# ICSL_PS_PCC_ATDE.net
KiCad netlist of a schematic drawn in Altium Designer
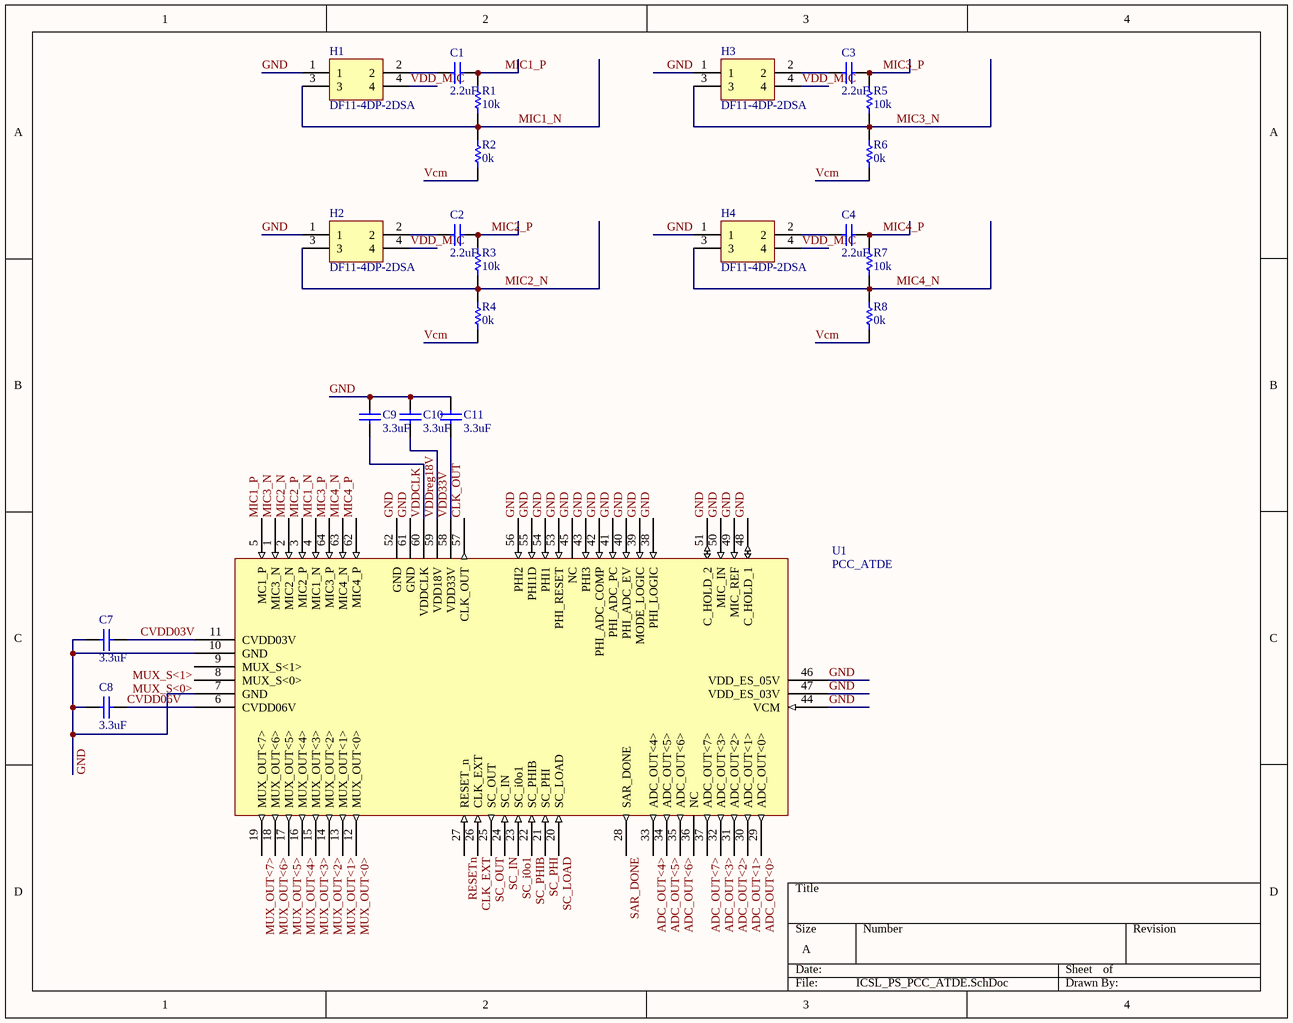
[diagram p0: ICSL_PS_PCC_ATDE.SchDoc]

(export (version "E")
  (design (tool "Eeschema 10.0.6"))
  (components
    (comp (ref "C1")
      (value "2.2uF")
      (footprint "CAPC1608X90X35NL15T15")
      (description "Multilayer Ceramic Capacitors MLCC - SMD/SMT 0603 10uF 4VOLTS X5R 10%")
      (fields (field (name "MANUFACTURER PART NUMBER") "06034D106KAT2A") (field (name "TOLERANCE") "10 %"))
      (libsource (lib "CommunityVault") (part "CMP-4105021-1"))
    )
    (comp (ref "C2")
      (value "2.2uF")
      (footprint "CAPC1608X90X35NL15T15")
      (description "Multilayer Ceramic Capacitors MLCC - SMD/SMT 0603 10uF 4VOLTS X5R 10%")
      (fields (field (name "MANUFACTURER PART NUMBER") "06034D106KAT2A") (field (name "TOLERANCE") "10 %"))
      (libsource (lib "CommunityVault") (part "CMP-4105021-1"))
    )
    (comp (ref "C3")
      (value "2.2uF")
      (footprint "CAPC1608X90X35NL15T15")
      (description "Multilayer Ceramic Capacitors MLCC - SMD/SMT 0603 10uF 4VOLTS X5R 10%")
      (fields (field (name "MANUFACTURER PART NUMBER") "06034D106KAT2A") (field (name "TOLERANCE") "10 %"))
      (libsource (lib "CommunityVault") (part "CMP-4105021-1"))
    )
    (comp (ref "C4")
      (value "2.2uF")
      (footprint "CAPC1608X90X35NL15T15")
      (description "Multilayer Ceramic Capacitors MLCC - SMD/SMT 0603 10uF 4VOLTS X5R 10%")
      (fields (field (name "MANUFACTURER PART NUMBER") "06034D106KAT2A") (field (name "TOLERANCE") "10 %"))
      (libsource (lib "CommunityVault") (part "CMP-4105021-1"))
    )
    (comp (ref "C7")
      (value "3.3uF")
      (footprint "CAPC1608X90X35NL15T15")
      (description "Multilayer Ceramic Capacitors MLCC - SMD/SMT 0603 10uF 4VOLTS X5R 10%")
      (fields (field (name "MANUFACTURER PART NUMBER") "06034D106KAT2A") (field (name "TOLERANCE") "10 %"))
      (libsource (lib "CommunityVault") (part "CMP-4105021-1"))
    )
    (comp (ref "C8")
      (value "3.3uF")
      (footprint "CAPC1608X90X35NL15T15")
      (description "Multilayer Ceramic Capacitors MLCC - SMD/SMT 0603 10uF 4VOLTS X5R 10%")
      (fields (field (name "MANUFACTURER PART NUMBER") "06034D106KAT2A") (field (name "TOLERANCE") "10 %"))
      (libsource (lib "CommunityVault") (part "CMP-4105021-1"))
    )
    (comp (ref "C9")
      (value "3.3uF")
      (footprint "CAPC1608X90X35NL15T15")
      (description "Multilayer Ceramic Capacitors MLCC - SMD/SMT 0603 10uF 4VOLTS X5R 10%")
      (fields (field (name "MANUFACTURER PART NUMBER") "06034D106KAT2A") (field (name "TOLERANCE") "10 %"))
      (libsource (lib "CommunityVault") (part "CMP-4105021-1"))
    )
    (comp (ref "C10")
      (value "3.3uF")
      (footprint "CAPC1608X90X35NL15T15")
      (description "Multilayer Ceramic Capacitors MLCC - SMD/SMT 0603 10uF 4VOLTS X5R 10%")
      (fields (field (name "MANUFACTURER PART NUMBER") "06034D106KAT2A") (field (name "TOLERANCE") "10 %"))
      (libsource (lib "CommunityVault") (part "CMP-4105021-1"))
    )
    (comp (ref "C11")
      (value "3.3uF")
      (footprint "CAPC1608X90X35NL15T15")
      (description "Multilayer Ceramic Capacitors MLCC - SMD/SMT 0603 10uF 4VOLTS X5R 10%")
      (fields (field (name "MANUFACTURER PART NUMBER") "06034D106KAT2A") (field (name "TOLERANCE") "10 %"))
      (libsource (lib "CommunityVault") (part "CMP-4105021-1"))
    )
    (comp (ref "H1")
      (value "DF11-4DP-2DSA")
      (footprint "PCB-xg1cw1zwm1fua28k7qwq-1")
      (description "4 Position 2mm Pitch Dual Row (2x2) Straight Through Hole Pin Header")
      (libsource (lib "Octopart library") (part "SYM-6dfba4f2b6fab23c-1"))
    )
    (comp (ref "H2")
      (value "DF11-4DP-2DSA")
      (footprint "PCB-xg1cw1zwm1fua28k7qwq-1")
      (description "4 Position 2mm Pitch Dual Row (2x2) Straight Through Hole Pin Header")
      (libsource (lib "Octopart library") (part "SYM-6dfba4f2b6fab23c-1"))
    )
    (comp (ref "H3")
      (value "DF11-4DP-2DSA")
      (footprint "PCB-xg1cw1zwm1fua28k7qwq-1")
      (description "4 Position 2mm Pitch Dual Row (2x2) Straight Through Hole Pin Header")
      (libsource (lib "Octopart library") (part "SYM-6dfba4f2b6fab23c-1"))
    )
    (comp (ref "H4")
      (value "DF11-4DP-2DSA")
      (footprint "PCB-xg1cw1zwm1fua28k7qwq-1")
      (description "4 Position 2mm Pitch Dual Row (2x2) Straight Through Hole Pin Header")
      (libsource (lib "Octopart library") (part "SYM-6dfba4f2b6fab23c-1"))
    )
    (comp (ref "R1")
      (value "10k")
      (footprint "RESC1609X50X30NL10T20")
      (description "RES SMD OHM 5% 1/10W 0603")
      (libsource (lib "CommunityVault") (part "CMP-1856112-2"))
    )
    (comp (ref "R2")
      (value "0k")
      (footprint "RESC1609X50X30NL10T20")
      (description "RES SMD 2.2M OHM 5% 1/10W 0603")
      (libsource (lib "CommunityVault") (part "CMP-1856112-2"))
    )
    (comp (ref "R3")
      (value "10k")
      (footprint "RESC1609X50X30NL10T20")
      (description "RES SMD OHM 5% 1/10W 0603")
      (libsource (lib "CommunityVault") (part "CMP-1856112-2"))
    )
    (comp (ref "R4")
      (value "0k")
      (footprint "RESC1609X50X30NL10T20")
      (description "RES SMD 2.2M OHM 5% 1/10W 0603")
      (libsource (lib "CommunityVault") (part "CMP-1856112-2"))
    )
    (comp (ref "R5")
      (value "10k")
      (footprint "RESC1609X50X30NL10T20")
      (description "RES SMD 2.2M OHM 5% 1/10W 0603")
      (libsource (lib "CommunityVault") (part "CMP-1856112-2"))
    )
    (comp (ref "R6")
      (value "0k")
      (footprint "RESC1609X50X30NL10T20")
      (description "RES SMD 2.2M OHM 5% 1/10W 0603")
      (libsource (lib "CommunityVault") (part "CMP-1856112-2"))
    )
    (comp (ref "R7")
      (value "10k")
      (footprint "RESC1609X50X30NL10T20")
      (description "RES SMD  OHM 5% 1/10W 0603")
      (libsource (lib "CommunityVault") (part "CMP-1856112-2"))
    )
    (comp (ref "R8")
      (value "0k")
      (footprint "RESC1609X50X30NL10T20")
      (description "RES SMD 2.2M OHM 5% 1/10W 0603")
      (libsource (lib "CommunityVault") (part "CMP-1856112-2"))
    )
    (comp (ref "U1")
      (value "PCC_ATDE")
      (footprint "Quad64")
      (description "ASP")
      (libsource (lib "FavoritesLibrary") (part "SYM-47mcin27x3h8n761pmad-1"))
    )
  )
  (nets
    (net (code "1") (name "/ADC_OUT<0>") (class "Default")
      (node (ref "U1") (pin "29") (pinfunction "ADC_OUT<0>_29") (pintype "output"))
    )
    (net (code "2") (name "/ADC_OUT<1>") (class "Default")
      (node (ref "U1") (pin "30") (pinfunction "ADC_OUT<1>_30") (pintype "output"))
    )
    (net (code "3") (name "/ADC_OUT<2>") (class "Default")
      (node (ref "U1") (pin "31") (pinfunction "ADC_OUT<2>_31") (pintype "output"))
    )
    (net (code "4") (name "/ADC_OUT<3>") (class "Default")
      (node (ref "U1") (pin "32") (pinfunction "ADC_OUT<3>_32") (pintype "output"))
    )
    (net (code "5") (name "/ADC_OUT<4>") (class "Default")
      (node (ref "U1") (pin "33") (pinfunction "ADC_OUT<4>_33") (pintype "output"))
    )
    (net (code "6") (name "/ADC_OUT<5>") (class "Default")
      (node (ref "U1") (pin "34") (pinfunction "ADC_OUT<5>_34") (pintype "output"))
    )
    (net (code "7") (name "/ADC_OUT<6>") (class "Default")
      (node (ref "U1") (pin "35") (pinfunction "ADC_OUT<6>_35") (pintype "output"))
    )
    (net (code "8") (name "/ADC_OUT<7>") (class "Default")
      (node (ref "U1") (pin "37") (pinfunction "ADC_OUT<7>_37") (pintype "output"))
    )
    (net (code "9") (name "/CLK_EXT") (class "Default")
      (node (ref "U1") (pin "26") (pinfunction "CLK_EXT_26") (pintype "input"))
    )
    (net (code "10") (name "/CLK_OUT") (class "Default")
      (node (ref "U1") (pin "57") (pinfunction "CLK_OUT_57") (pintype "output"))
    )
    (net (code "11") (name "/CVDD03V") (class "Default")
      (node (ref "C7") (pin "1") (pinfunction "1_1") (pintype "passive"))
      (node (ref "U1") (pin "11") (pinfunction "CVDD03V_11") (pintype "power_in"))
    )
    (net (code "12") (name "/CVDD06V") (class "Default")
      (node (ref "C8") (pin "1") (pinfunction "1_1") (pintype "passive"))
      (node (ref "U1") (pin "6") (pinfunction "CVDD06V_6") (pintype "power_in"))
    )
    (net (code "13") (name "/GND") (class "Default")
      (node (ref "C10") (pin "1") (pinfunction "1_1") (pintype "passive"))
      (node (ref "C11") (pin "1") (pinfunction "1_1") (pintype "passive"))
      (node (ref "C7") (pin "2") (pinfunction "2_2") (pintype "passive"))
      (node (ref "C8") (pin "2") (pinfunction "2_2") (pintype "passive"))
      (node (ref "C9") (pin "2") (pinfunction "2_2") (pintype "passive"))
      (node (ref "H1") (pin "1") (pinfunction "1_1") (pintype "passive"))
      (node (ref "H2") (pin "1") (pinfunction "1_1") (pintype "passive"))
      (node (ref "H3") (pin "1") (pinfunction "1_1") (pintype "passive"))
      (node (ref "H4") (pin "1") (pinfunction "1_1") (pintype "passive"))
      (node (ref "U1") (pin "10") (pinfunction "GND_10") (pintype "passive"))
      (node (ref "U1") (pin "38") (pinfunction "PHI_LOGIC_38") (pintype "input"))
      (node (ref "U1") (pin "39") (pinfunction "MODE_LOGIC_39") (pintype "input"))
      (node (ref "U1") (pin "40") (pinfunction "PHI_ADC_EV_40") (pintype "input"))
      (node (ref "U1") (pin "41") (pinfunction "PHI_ADC_PC_41") (pintype "input"))
      (node (ref "U1") (pin "42") (pinfunction "PHI_ADC_COMP_42") (pintype "input"))
      (node (ref "U1") (pin "43") (pinfunction "PHI3_43") (pintype "input"))
      (node (ref "U1") (pin "44") (pinfunction "VCM_44") (pintype "input"))
      (node (ref "U1") (pin "45") (pinfunction "NC_45") (pintype "passive"))
      (node (ref "U1") (pin "46") (pinfunction "VDD_ES_05V_46") (pintype "passive"))
      (node (ref "U1") (pin "47") (pinfunction "VDD_ES_03V_47") (pintype "passive"))
      (node (ref "U1") (pin "48") (pinfunction "C_HOLD_1_48") (pintype "bidirectional"))
      (node (ref "U1") (pin "49") (pinfunction "MIC_REF_49") (pintype "input"))
      (node (ref "U1") (pin "50") (pinfunction "MIC_IN_50") (pintype "input"))
      (node (ref "U1") (pin "51") (pinfunction "C_HOLD_2_51") (pintype "bidirectional"))
      (node (ref "U1") (pin "52") (pinfunction "GND_52") (pintype "passive"))
      (node (ref "U1") (pin "53") (pinfunction "PHI_RESET_53") (pintype "input"))
      (node (ref "U1") (pin "54") (pinfunction "PHI1_54") (pintype "input"))
      (node (ref "U1") (pin "55") (pinfunction "PHI1D_55") (pintype "input"))
      (node (ref "U1") (pin "56") (pinfunction "PHI2_56") (pintype "input"))
      (node (ref "U1") (pin "61") (pinfunction "GND_61") (pintype "passive"))
      (node (ref "U1") (pin "7") (pinfunction "GND_7") (pintype "power_in"))
    )
    (net (code "14") (name "/MIC1_N") (class "Default")
      (node (ref "H1") (pin "3") (pinfunction "3_3") (pintype "passive"))
      (node (ref "R1") (pin "2") (pinfunction "2_2") (pintype "passive"))
      (node (ref "R2") (pin "2") (pinfunction "2_2") (pintype "passive"))
      (node (ref "U1") (pin "4") (pinfunction "MIC1_N_4") (pintype "input"))
    )
    (net (code "15") (name "/MIC1_P") (class "Default")
      (node (ref "C1") (pin "2") (pinfunction "2_2") (pintype "passive"))
      (node (ref "R1") (pin "1") (pinfunction "1_1") (pintype "passive"))
      (node (ref "U1") (pin "5") (pinfunction "MC1_P_5") (pintype "input"))
    )
    (net (code "16") (name "/MIC2_N") (class "Default")
      (node (ref "H2") (pin "3") (pinfunction "3_3") (pintype "passive"))
      (node (ref "R3") (pin "2") (pinfunction "2_2") (pintype "passive"))
      (node (ref "R4") (pin "2") (pinfunction "2_2") (pintype "passive"))
      (node (ref "U1") (pin "2") (pinfunction "MIC2_N_2") (pintype "input"))
    )
    (net (code "17") (name "/MIC2_P") (class "Default")
      (node (ref "C2") (pin "2") (pinfunction "2_2") (pintype "passive"))
      (node (ref "R3") (pin "1") (pinfunction "1_1") (pintype "passive"))
      (node (ref "U1") (pin "3") (pinfunction "MIC2_P_3") (pintype "input"))
    )
    (net (code "18") (name "/MIC3_N") (class "Default")
      (node (ref "H3") (pin "3") (pinfunction "3_3") (pintype "passive"))
      (node (ref "R5") (pin "2") (pinfunction "2_2") (pintype "passive"))
      (node (ref "R6") (pin "2") (pinfunction "2_2") (pintype "passive"))
      (node (ref "U1") (pin "1") (pinfunction "MIC3_N_1") (pintype "input"))
    )
    (net (code "19") (name "/MIC3_P") (class "Default")
      (node (ref "C3") (pin "2") (pinfunction "2_2") (pintype "passive"))
      (node (ref "R5") (pin "1") (pinfunction "1_1") (pintype "passive"))
      (node (ref "U1") (pin "64") (pinfunction "MIC3_P_64") (pintype "input"))
    )
    (net (code "20") (name "/MIC4_N") (class "Default")
      (node (ref "H4") (pin "3") (pinfunction "3_3") (pintype "passive"))
      (node (ref "R7") (pin "2") (pinfunction "2_2") (pintype "passive"))
      (node (ref "R8") (pin "2") (pinfunction "2_2") (pintype "passive"))
      (node (ref "U1") (pin "63") (pinfunction "MIC4_N_63") (pintype "input"))
    )
    (net (code "21") (name "/MIC4_P") (class "Default")
      (node (ref "C4") (pin "2") (pinfunction "2_2") (pintype "passive"))
      (node (ref "R7") (pin "1") (pinfunction "1_1") (pintype "passive"))
      (node (ref "U1") (pin "62") (pinfunction "MIC4_P_62") (pintype "input"))
    )
    (net (code "22") (name "/MUX_OUT<0>") (class "Default")
      (node (ref "U1") (pin "12") (pinfunction "MUX_OUT<0>_12") (pintype "output"))
    )
    (net (code "23") (name "/MUX_OUT<1>") (class "Default")
      (node (ref "U1") (pin "13") (pinfunction "MUX_OUT<1>_13") (pintype "output"))
    )
    (net (code "24") (name "/MUX_OUT<2>") (class "Default")
      (node (ref "U1") (pin "14") (pinfunction "MUX_OUT<2>_14") (pintype "output"))
    )
    (net (code "25") (name "/MUX_OUT<3>") (class "Default")
      (node (ref "U1") (pin "15") (pinfunction "MUX_OUT<3>_15") (pintype "output"))
    )
    (net (code "26") (name "/MUX_OUT<4>") (class "Default")
      (node (ref "U1") (pin "16") (pinfunction "MUX_OUT<4>_16") (pintype "output"))
    )
    (net (code "27") (name "/MUX_OUT<5>") (class "Default")
      (node (ref "U1") (pin "17") (pinfunction "MUX_OUT<5>_17") (pintype "output"))
    )
    (net (code "28") (name "/MUX_OUT<6>") (class "Default")
      (node (ref "U1") (pin "18") (pinfunction "MUX_OUT<6>_18") (pintype "output"))
    )
    (net (code "29") (name "/MUX_OUT<7>") (class "Default")
      (node (ref "U1") (pin "19") (pinfunction "MUX_OUT<7>_19") (pintype "output"))
    )
    (net (code "30") (name "/MUX_S<0>") (class "Default")
      (node (ref "U1") (pin "8") (pinfunction "MUX_S<0>_8") (pintype "passive"))
    )
    (net (code "31") (name "/MUX_S<1>") (class "Default")
      (node (ref "U1") (pin "9") (pinfunction "MUX_S<1>_9") (pintype "passive"))
    )
    (net (code "32") (name "/RESETn") (class "Default")
      (node (ref "U1") (pin "27") (pinfunction "RESET_n_27") (pintype "input"))
    )
    (net (code "33") (name "/SAR_DONE") (class "Default")
      (node (ref "U1") (pin "28") (pinfunction "SAR_DONE_28") (pintype "output"))
    )
    (net (code "34") (name "/SC_IN") (class "Default")
      (node (ref "U1") (pin "24") (pinfunction "SC_IN_24") (pintype "input"))
    )
    (net (code "35") (name "/SC_LOAD") (class "Default")
      (node (ref "U1") (pin "20") (pinfunction "SC_LOAD_20") (pintype "input"))
    )
    (net (code "36") (name "/SC_OUT") (class "Default")
      (node (ref "U1") (pin "25") (pinfunction "SC_OUT_25") (pintype "output"))
    )
    (net (code "37") (name "/SC_PHI") (class "Default")
      (node (ref "U1") (pin "21") (pinfunction "SC_PHI_21") (pintype "input"))
    )
    (net (code "38") (name "/SC_PHIB") (class "Default")
      (node (ref "U1") (pin "22") (pinfunction "SC_PHIB_22") (pintype "input"))
    )
    (net (code "39") (name "/SC_i0o1") (class "Default")
      (node (ref "U1") (pin "23") (pinfunction "SC_i0o1_23") (pintype "input"))
    )
    (net (code "40") (name "/VDD33V") (class "Default")
      (node (ref "C11") (pin "2") (pinfunction "2_2") (pintype "passive"))
      (node (ref "U1") (pin "58") (pinfunction "VDD33V_58") (pintype "passive"))
    )
    (net (code "41") (name "/VDDCLK") (class "Default")
      (node (ref "C9") (pin "1") (pinfunction "1_1") (pintype "passive"))
      (node (ref "U1") (pin "60") (pinfunction "VDDCLK_60") (pintype "passive"))
    )
    (net (code "42") (name "/VDD_MIC") (class "Default")
      (node (ref "H1") (pin "4") (pinfunction "4_4") (pintype "passive"))
      (node (ref "H2") (pin "4") (pinfunction "4_4") (pintype "passive"))
      (node (ref "H3") (pin "4") (pinfunction "4_4") (pintype "passive"))
      (node (ref "H4") (pin "4") (pinfunction "4_4") (pintype "passive"))
    )
    (net (code "43") (name "/VDDreg18V") (class "Default")
      (node (ref "C10") (pin "2") (pinfunction "2_2") (pintype "passive"))
      (node (ref "U1") (pin "59") (pinfunction "VDD18V_59") (pintype "passive"))
    )
    (net (code "44") (name "/Vcm") (class "Default")
      (node (ref "R2") (pin "1") (pinfunction "1_1") (pintype "passive"))
      (node (ref "R4") (pin "1") (pinfunction "1_1") (pintype "passive"))
      (node (ref "R6") (pin "1") (pinfunction "1_1") (pintype "passive"))
      (node (ref "R8") (pin "1") (pinfunction "1_1") (pintype "passive"))
    )
    (net (code "45") (name "Net-(C1-Pad1)") (class "Default")
      (node (ref "C1") (pin "1") (pinfunction "1_1") (pintype "passive"))
      (node (ref "H1") (pin "2") (pinfunction "2_2") (pintype "passive"))
    )
    (net (code "46") (name "Net-(C2-Pad1)") (class "Default")
      (node (ref "C2") (pin "1") (pinfunction "1_1") (pintype "passive"))
      (node (ref "H2") (pin "2") (pinfunction "2_2") (pintype "passive"))
    )
    (net (code "47") (name "Net-(C3-Pad1)") (class "Default")
      (node (ref "C3") (pin "1") (pinfunction "1_1") (pintype "passive"))
      (node (ref "H3") (pin "2") (pinfunction "2_2") (pintype "passive"))
    )
    (net (code "48") (name "Net-(C4-Pad1)") (class "Default")
      (node (ref "C4") (pin "1") (pinfunction "1_1") (pintype "passive"))
      (node (ref "H4") (pin "2") (pinfunction "2_2") (pintype "passive"))
    )
    (net (code "49") (name "unconnected-(U1-NC-Pad36)") (class "Default")
      (node (ref "U1") (pin "36") (pinfunction "NC_36") (pintype "passive"))
    )
  )
)
